# easyeda.net
KiCad netlist of a schematic drawn in EasyEDA
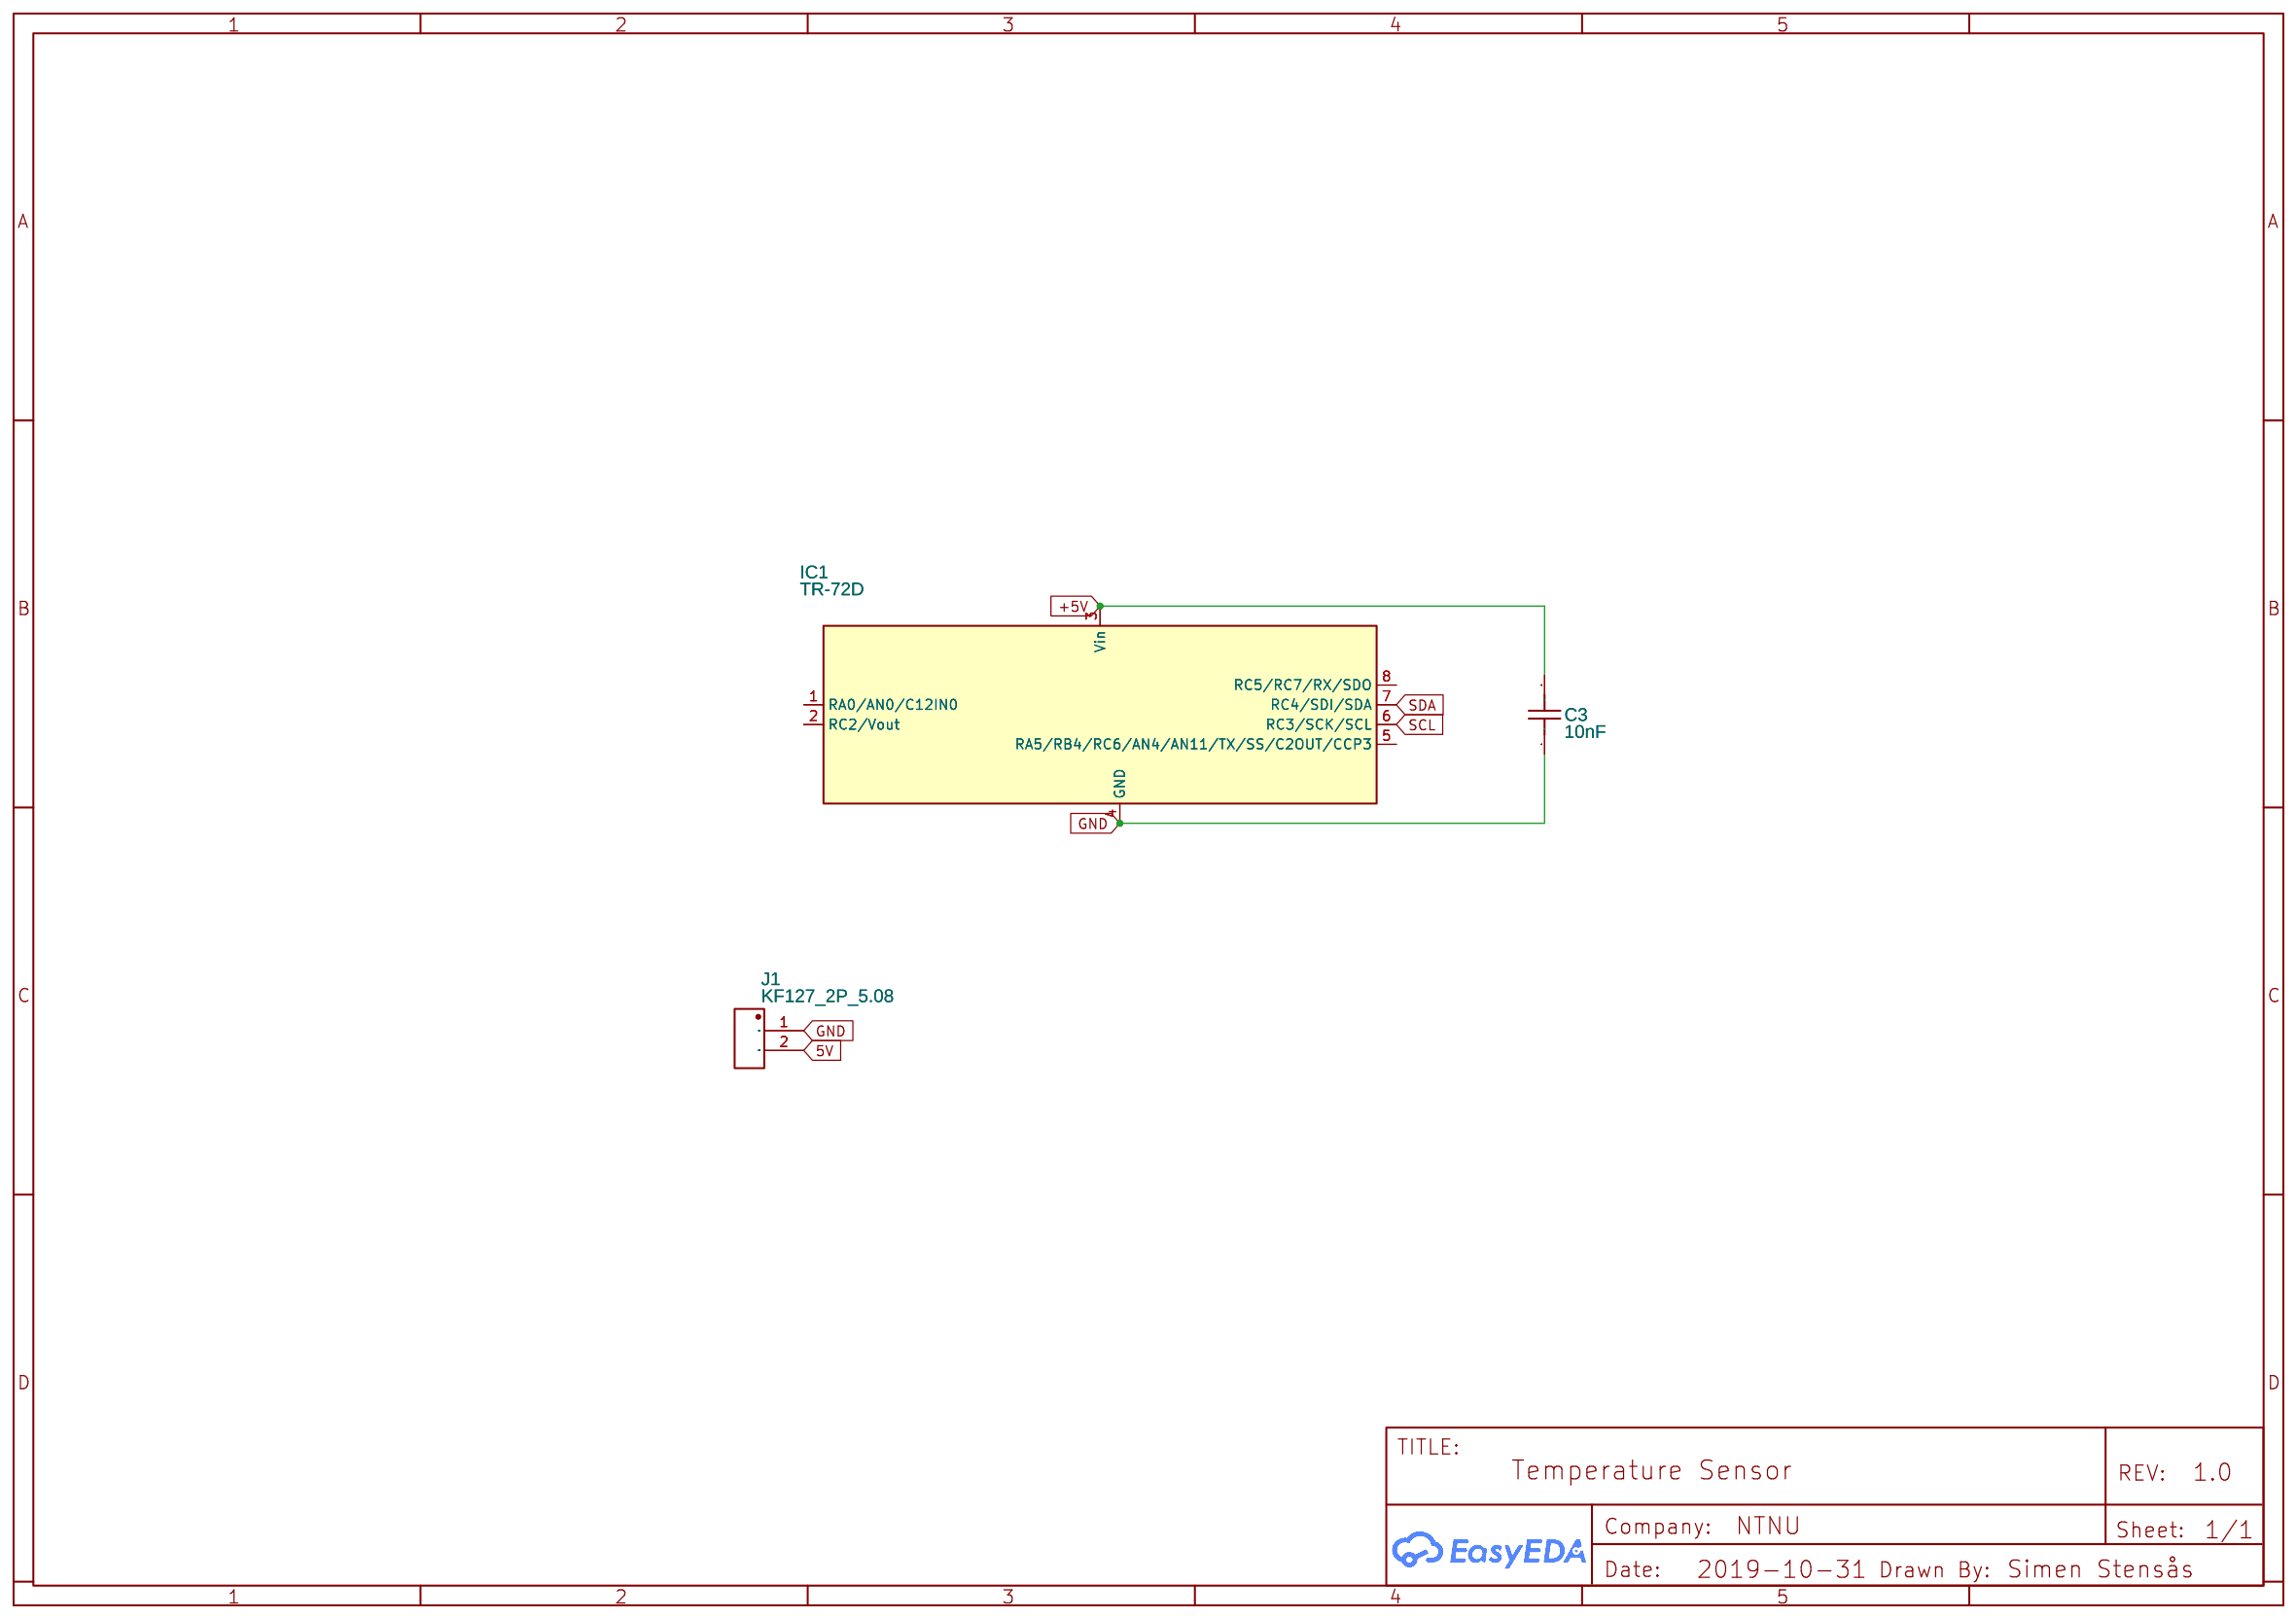
[diagram p0: schematic sheet]

(export (version "E")
  (design (tool "Eeschema 10.0.6"))
  (components
    (comp (ref "C3")
      (value "10nF")
      (fields
        (field (name "BOM_Manufacturer Part") "0603B103K500AT")
        (field (name "BOM_Supplier Part") "C327421")
      )
      (libsource (lib "") (part "0603B103K500AT"))
    )
    (comp (ref "IC1") (value "TR-72D") (libsource (lib "") (part "Unknown_410_350")))
    (comp (ref "J1")
      (value "KF127_2P_5.08")
      (fields (field (name "BOM_Manufacturer Part") "KF127L-5.08"))
      (libsource (lib "") (part "Unknown_385_520"))
    )
  )
  (nets
    (net (code "1") (name "+5V") (class "Default")
      (node (ref "C3") (pin "2") (pinfunction "2_2") (pintype "unspecified"))
      (node (ref "IC1") (pin "3") (pinfunction "Vin_3") (pintype "bidirectional"))
    )
    (net (code "2") (name "5V") (class "Default")
      (node (ref "J1") (pin "2") (pinfunction "PIN2_2") (pintype "unspecified"))
    )
    (net (code "3") (name "GND") (class "Default")
      (node (ref "C3") (pin "1") (pinfunction "1_1") (pintype "unspecified"))
      (node (ref "IC1") (pin "4") (pinfunction "GND_4") (pintype "bidirectional"))
      (node (ref "J1") (pin "1") (pinfunction "PIN1_1") (pintype "unspecified"))
    )
    (net (code "4") (name "SCL") (class "Default")
      (node (ref "IC1") (pin "6") (pinfunction "RC3/SCK/SCL_6") (pintype "bidirectional"))
    )
    (net (code "5") (name "SDA") (class "Default")
      (node (ref "IC1") (pin "7") (pinfunction "RC4/SDI/SDA_7") (pintype "bidirectional"))
    )
    (net (code "6") (name "unconnected-(IC1-RA0{slash}AN0{slash}C12IN0-Pad1)") (class "Default")
      (node (ref "IC1") (pin "1") (pinfunction "RA0/AN0/C12IN0_1") (pintype "bidirectional"))
    )
    (net (code "7") (name "unconnected-(IC1-RA5{slash}RB4{slash}RC6{slash}AN4{slash}AN11{slash}TX{slash}SS{slash}C2OUT{slash}CCP3-Pad5)") (class "Default")
      (node (ref "IC1") (pin "5") (pinfunction "RA5/RB4/RC6/AN4/AN11/TX/SS/C2OUT/CCP3_5") (pintype "bidirectional"))
    )
    (net (code "8") (name "unconnected-(IC1-RC2{slash}Vout-Pad2)") (class "Default")
      (node (ref "IC1") (pin "2") (pinfunction "RC2/Vout_2") (pintype "bidirectional"))
    )
    (net (code "9") (name "unconnected-(IC1-RC5{slash}RC7{slash}RX{slash}SDO-Pad8)") (class "Default")
      (node (ref "IC1") (pin "8") (pinfunction "RC5/RC7/RX/SDO_8") (pintype "bidirectional"))
    )
  )
)
